# RGB_Light.net
KiCad netlist of a schematic drawn in EAGLE
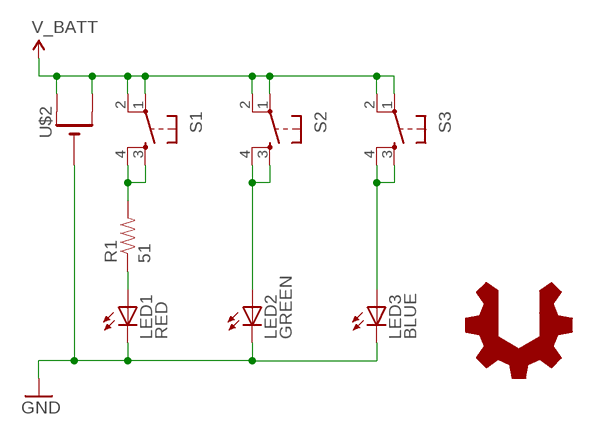
[diagram p0: schematic, sheet 1]

(export (version "E")
  (design (tool "Eeschema 10.0.6"))
  (components
    (comp (ref "LED1")
      (value "RED")
      (footprint "eagle-import:LED-OVAL")
      (libsource (lib "eagle-import") (part "LEDOVAL"))
    )
    (comp (ref "LED2")
      (value "GREEN")
      (footprint "eagle-import:LED-OVAL")
      (libsource (lib "eagle-import") (part "LEDOVAL"))
    )
    (comp (ref "LED3")
      (value "BLUE")
      (footprint "eagle-import:LED-OVAL")
      (libsource (lib "eagle-import") (part "LEDOVAL"))
    )
    (comp (ref "R1")
      (value "51")
      (footprint "eagle-import:AXIAL-0.3")
      (libsource (lib "eagle-import") (part "RESISTORAXIAL-0.3"))
    )
    (comp (ref "S1")
      (value "TAC_SWITCHPTH")
      (footprint "eagle-import:TACTILE-PTH")
      (libsource (lib "eagle-import") (part "TAC_SWITCHPTH"))
    )
    (comp (ref "S2")
      (value "TAC_SWITCHPTH")
      (footprint "eagle-import:TACTILE-PTH")
      (libsource (lib "eagle-import") (part "TAC_SWITCHPTH"))
    )
    (comp (ref "S3")
      (value "TAC_SWITCHPTH")
      (footprint "eagle-import:TACTILE-PTH")
      (libsource (lib "eagle-import") (part "TAC_SWITCHPTH"))
    )
    (comp (ref "U$1")
      (value "USER_HACKABLE")
      (footprint "eagle-import:USER_HACKABLE")
      (libsource (lib "eagle-import") (part "USER_HACKABLE"))
    )
    (comp (ref "U$2")
      (value "CR2032THM")
      (footprint "eagle-import:CR2032-THRU")
      (libsource (lib "eagle-import") (part "CR2032THM"))
    )
  )
  (nets
    (net (code "1") (name "GND") (class "Default")
      (node (ref "LED1") (pin "CATHODE") (pinfunction "C_CATHODE") (pintype "passive"))
      (node (ref "LED2") (pin "CATHODE") (pinfunction "C_CATHODE") (pintype "passive"))
      (node (ref "LED3") (pin "CATHODE") (pinfunction "C_CATHODE") (pintype "passive"))
      (node (ref "U$2") (pin "-") (pinfunction "-_-") (pintype "passive"))
    )
    (net (code "2") (name "Net-(LED1-A)") (class "Default")
      (node (ref "LED1") (pin "ANODE") (pinfunction "A_ANODE") (pintype "passive"))
      (node (ref "R1") (pin "P$1") (pinfunction "1_P$1") (pintype "passive"))
    )
    (net (code "3") (name "Net-(LED2-A)") (class "Default")
      (node (ref "LED2") (pin "ANODE") (pinfunction "A_ANODE") (pintype "passive"))
      (node (ref "S2") (pin "3") (pinfunction "3_3") (pintype "passive"))
      (node (ref "S2") (pin "4") (pinfunction "4_4") (pintype "passive"))
    )
    (net (code "4") (name "Net-(LED3-A)") (class "Default")
      (node (ref "LED3") (pin "ANODE") (pinfunction "A_ANODE") (pintype "passive"))
      (node (ref "S3") (pin "3") (pinfunction "3_3") (pintype "passive"))
      (node (ref "S3") (pin "4") (pinfunction "4_4") (pintype "passive"))
    )
    (net (code "5") (name "Net-(R1-2)") (class "Default")
      (node (ref "R1") (pin "P$2") (pinfunction "2_P$2") (pintype "passive"))
      (node (ref "S1") (pin "3") (pinfunction "3_3") (pintype "passive"))
      (node (ref "S1") (pin "4") (pinfunction "4_4") (pintype "passive"))
    )
    (net (code "6") (name "V_BATT") (class "Default")
      (node (ref "S1") (pin "1") (pinfunction "1_1") (pintype "passive"))
      (node (ref "S1") (pin "2") (pinfunction "2_2") (pintype "passive"))
      (node (ref "S2") (pin "1") (pinfunction "1_1") (pintype "passive"))
      (node (ref "S2") (pin "2") (pinfunction "2_2") (pintype "passive"))
      (node (ref "S3") (pin "1") (pinfunction "1_1") (pintype "passive"))
      (node (ref "S3") (pin "2") (pinfunction "2_2") (pintype "passive"))
      (node (ref "U$2") (pin "+1") (pinfunction "+_+1") (pintype "passive"))
      (node (ref "U$2") (pin "+2") (pinfunction "+1_+2") (pintype "passive"))
    )
  )
)
